# Controller-IOBoard.net
KiCad netlist of a schematic drawn in Altium Designer
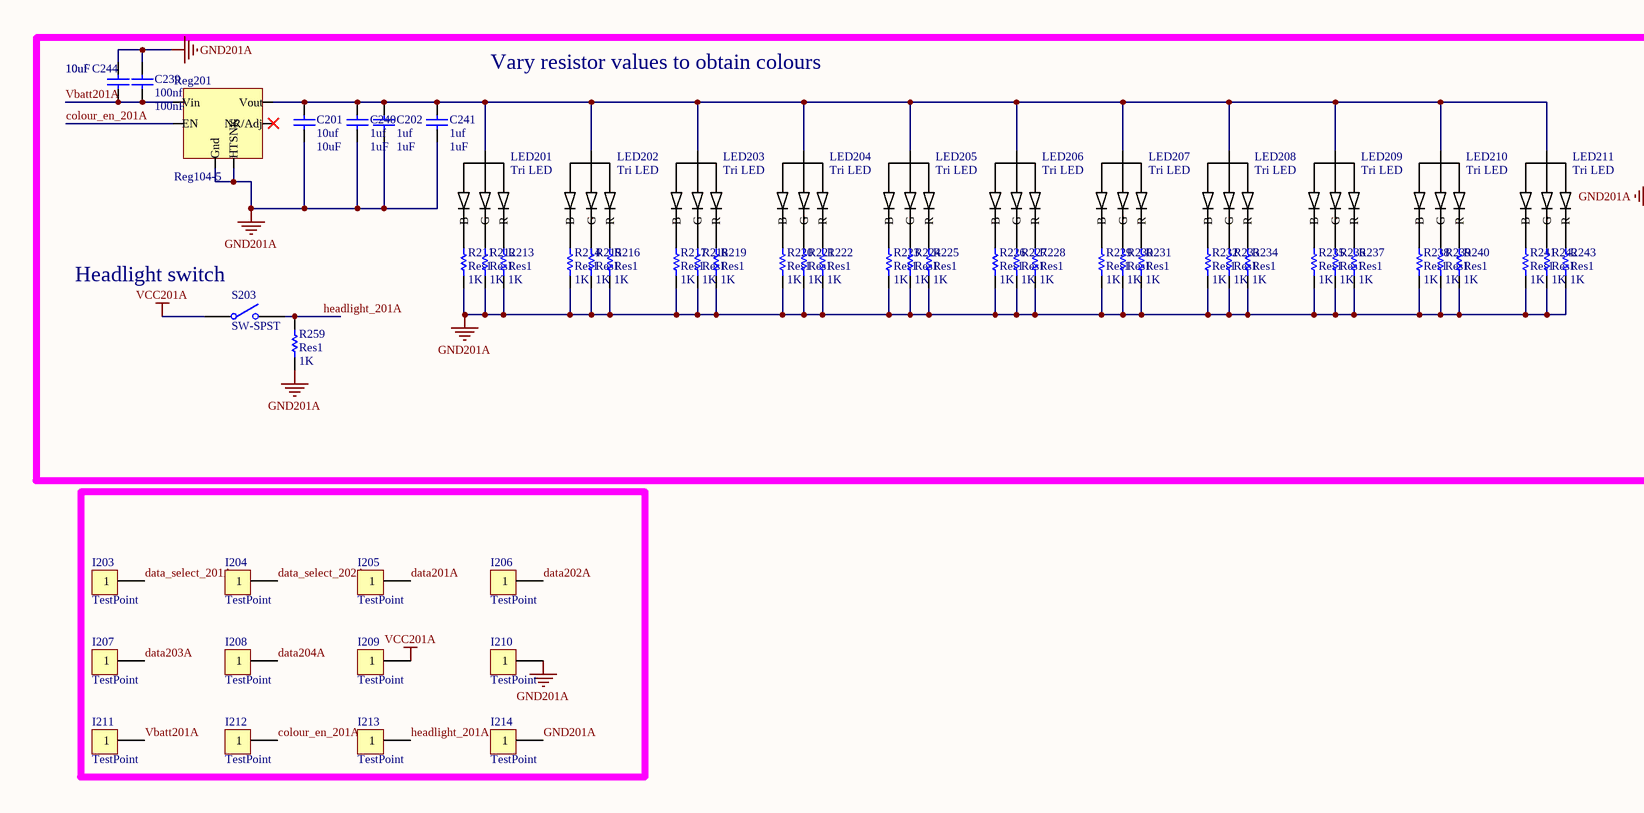
[diagram p0: Controller-IOBoard.SchDoc, left]
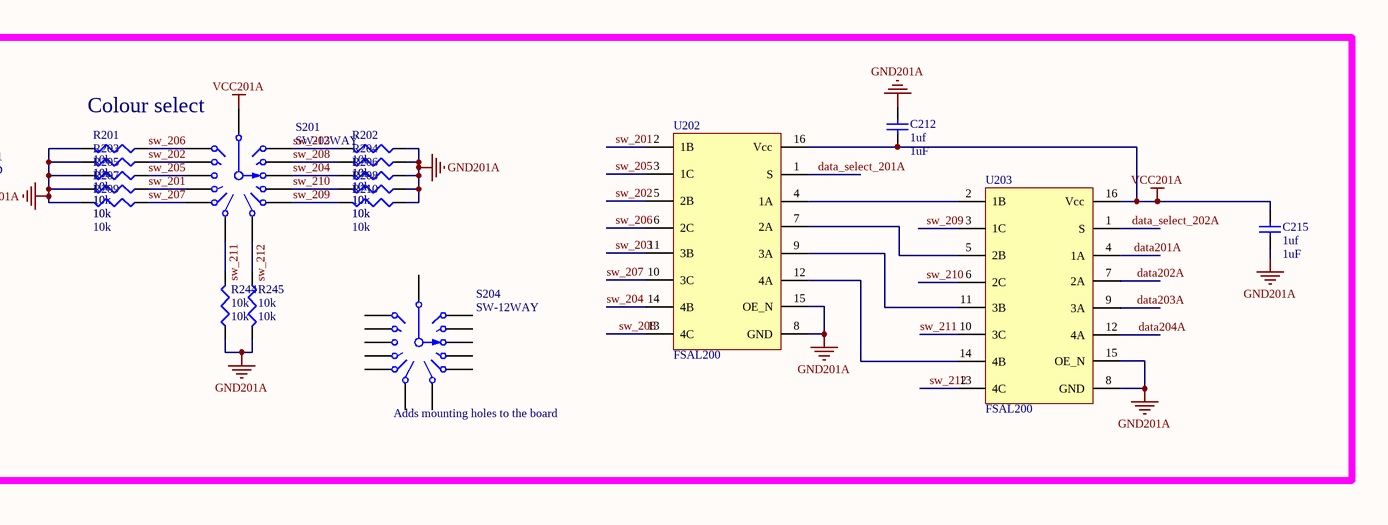
[diagram p1: Controller-IOBoard.SchDoc, right]

(export (version "E")
  (design (tool "Eeschema 10.0.6"))
  (components
    (comp (ref "C201")
      (value "10uf")
      (footprint "0805")
      (description "Capacitor (Semiconductor SIM Model)")
      (fields (field (name "ALTIUM_VALUE") "10uF") (field (name "PUBLISHER") "Altium Limited"))
      (libsource (lib "Miscellaneous Devices") (part "Cap Semi"))
    )
    (comp (ref "C202")
      (value "1uf")
      (footprint "0603")
      (description "Capacitor (Semiconductor SIM Model)")
      (fields (field (name "ALTIUM_VALUE") "1uF") (field (name "PUBLISHER") "Altium Limited"))
      (libsource (lib "Miscellaneous Devices") (part "Cap Semi"))
    )
    (comp (ref "C212")
      (value "1uf")
      (footprint "0603")
      (description "Capacitor (Semiconductor SIM Model)")
      (fields (field (name "ALTIUM_VALUE") "1uF") (field (name "PUBLISHER") "Altium Limited"))
      (libsource (lib "Miscellaneous Devices") (part "Cap Semi"))
    )
    (comp (ref "C215")
      (value "1uf")
      (footprint "0603")
      (description "Capacitor (Semiconductor SIM Model)")
      (fields (field (name "ALTIUM_VALUE") "1uF") (field (name "PUBLISHER") "Altium Limited"))
      (libsource (lib "Miscellaneous Devices") (part "Cap Semi"))
    )
    (comp (ref "C239")
      (value "100nf")
      (footprint "0603")
      (description "Capacitor (Semiconductor SIM Model)")
      (fields (field (name "ALTIUM_VALUE") "100nF") (field (name "PUBLISHER") "Altium Limited"))
      (libsource (lib "Miscellaneous Devices") (part "Cap Semi"))
    )
    (comp (ref "C240")
      (value "1uf")
      (footprint "0603")
      (description "Capacitor (Semiconductor SIM Model)")
      (fields (field (name "ALTIUM_VALUE") "1uF") (field (name "PUBLISHER") "Altium Limited"))
      (libsource (lib "Miscellaneous Devices") (part "Cap Semi"))
    )
    (comp (ref "C241")
      (value "1uf")
      (footprint "0603")
      (description "Capacitor (Semiconductor SIM Model)")
      (fields (field (name "ALTIUM_VALUE") "1uF") (field (name "PUBLISHER") "Altium Limited"))
      (libsource (lib "Miscellaneous Devices") (part "Cap Semi"))
    )
    (comp (ref "C244")
      (value "10uf")
      (footprint "0805")
      (description "Capacitor (Semiconductor SIM Model)")
      (fields (field (name "ALTIUM_VALUE") "10uF") (field (name "PUBLISHER") "Altium Limited"))
      (libsource (lib "Miscellaneous Devices") (part "Cap Semi"))
    )
    (comp (ref "I203")
      (value "TestPoint")
      (footprint "TestPoint")
      (libsource (lib "Schlib1") (part "TestPoint"))
    )
    (comp (ref "I204")
      (value "TestPoint")
      (footprint "TestPoint")
      (libsource (lib "Schlib1") (part "TestPoint"))
    )
    (comp (ref "I205")
      (value "TestPoint")
      (footprint "TestPoint")
      (libsource (lib "Schlib1") (part "TestPoint"))
    )
    (comp (ref "I206")
      (value "TestPoint")
      (footprint "TestPoint")
      (libsource (lib "Schlib1") (part "TestPoint"))
    )
    (comp (ref "I207")
      (value "TestPoint")
      (footprint "TestPoint")
      (libsource (lib "Schlib1") (part "TestPoint"))
    )
    (comp (ref "I208")
      (value "TestPoint")
      (footprint "TestPoint")
      (libsource (lib "Schlib1") (part "TestPoint"))
    )
    (comp (ref "I209")
      (value "TestPoint")
      (footprint "TestPoint")
      (libsource (lib "Schlib1") (part "TestPoint"))
    )
    (comp (ref "I210")
      (value "TestPoint")
      (footprint "TestPoint")
      (libsource (lib "Schlib1") (part "TestPoint"))
    )
    (comp (ref "I211")
      (value "TestPoint")
      (footprint "TestPoint")
      (libsource (lib "Schlib1") (part "TestPoint"))
    )
    (comp (ref "I212")
      (value "TestPoint")
      (footprint "TestPoint")
      (libsource (lib "Schlib1") (part "TestPoint"))
    )
    (comp (ref "I213")
      (value "TestPoint")
      (footprint "TestPoint")
      (libsource (lib "Schlib1") (part "TestPoint"))
    )
    (comp (ref "I214")
      (value "TestPoint")
      (footprint "TestPoint")
      (libsource (lib "Schlib1") (part "TestPoint"))
    )
    (comp (ref "LED201")
      (value "Tri LED")
      (footprint "CLV1A-FKB")
      (libsource (lib "Schlib1") (part "Tri LED"))
    )
    (comp (ref "LED202")
      (value "Tri LED")
      (footprint "CLV1A-FKB")
      (libsource (lib "Schlib1") (part "Tri LED"))
    )
    (comp (ref "LED203")
      (value "Tri LED")
      (footprint "CLV1A-FKB")
      (libsource (lib "Schlib1") (part "Tri LED"))
    )
    (comp (ref "LED204")
      (value "Tri LED")
      (footprint "CLV1A-FKB")
      (libsource (lib "Schlib1") (part "Tri LED"))
    )
    (comp (ref "LED205")
      (value "Tri LED")
      (footprint "CLV1A-FKB")
      (libsource (lib "Schlib1") (part "Tri LED"))
    )
    (comp (ref "LED206")
      (value "Tri LED")
      (footprint "CLV1A-FKB")
      (libsource (lib "Schlib1") (part "Tri LED"))
    )
    (comp (ref "LED207")
      (value "Tri LED")
      (footprint "CLV1A-FKB")
      (libsource (lib "Schlib1") (part "Tri LED"))
    )
    (comp (ref "LED208")
      (value "Tri LED")
      (footprint "CLV1A-FKB")
      (libsource (lib "Schlib1") (part "Tri LED"))
    )
    (comp (ref "LED209")
      (value "Tri LED")
      (footprint "CLV1A-FKB")
      (libsource (lib "Schlib1") (part "Tri LED"))
    )
    (comp (ref "LED210")
      (value "Tri LED")
      (footprint "CLV1A-FKB")
      (libsource (lib "Schlib1") (part "Tri LED"))
    )
    (comp (ref "LED211")
      (value "Tri LED")
      (footprint "CLV1A-FKB")
      (libsource (lib "Schlib1") (part "Tri LED"))
    )
    (comp (ref "R201")
      (value "10k")
      (footprint "0603")
      (description "Resistor")
      (fields (field (name "ALTIUM_VALUE") "10k") (field (name "PUBLISHER") "Altium Limited"))
      (libsource (lib "Miscellaneous Devices") (part "Res3"))
    )
    (comp (ref "R202")
      (value "10k")
      (footprint "0603")
      (description "Resistor")
      (fields (field (name "ALTIUM_VALUE") "10k") (field (name "PUBLISHER") "Altium Limited"))
      (libsource (lib "Miscellaneous Devices") (part "Res3"))
    )
    (comp (ref "R203")
      (value "10k")
      (footprint "0603")
      (description "Resistor")
      (fields (field (name "ALTIUM_VALUE") "10k") (field (name "PUBLISHER") "Altium Limited"))
      (libsource (lib "Miscellaneous Devices") (part "Res3"))
    )
    (comp (ref "R204")
      (value "10k")
      (footprint "0603")
      (description "Resistor")
      (fields (field (name "ALTIUM_VALUE") "10k") (field (name "PUBLISHER") "Altium Limited"))
      (libsource (lib "Miscellaneous Devices") (part "Res3"))
    )
    (comp (ref "R205")
      (value "10k")
      (footprint "0603")
      (description "Resistor")
      (fields (field (name "ALTIUM_VALUE") "10k") (field (name "PUBLISHER") "Altium Limited"))
      (libsource (lib "Miscellaneous Devices") (part "Res3"))
    )
    (comp (ref "R206")
      (value "10k")
      (footprint "0603")
      (description "Resistor")
      (fields (field (name "ALTIUM_VALUE") "10k") (field (name "PUBLISHER") "Altium Limited"))
      (libsource (lib "Miscellaneous Devices") (part "Res3"))
    )
    (comp (ref "R207")
      (value "10k")
      (footprint "0603")
      (description "Resistor")
      (fields (field (name "ALTIUM_VALUE") "10k") (field (name "PUBLISHER") "Altium Limited"))
      (libsource (lib "Miscellaneous Devices") (part "Res3"))
    )
    (comp (ref "R208")
      (value "10k")
      (footprint "0603")
      (description "Resistor")
      (fields (field (name "ALTIUM_VALUE") "10k") (field (name "PUBLISHER") "Altium Limited"))
      (libsource (lib "Miscellaneous Devices") (part "Res3"))
    )
    (comp (ref "R209")
      (value "10k")
      (footprint "0603")
      (description "Resistor")
      (fields (field (name "ALTIUM_VALUE") "10k") (field (name "PUBLISHER") "Altium Limited"))
      (libsource (lib "Miscellaneous Devices") (part "Res3"))
    )
    (comp (ref "R210")
      (value "10k")
      (footprint "0603")
      (description "Resistor")
      (fields (field (name "ALTIUM_VALUE") "10k") (field (name "PUBLISHER") "Altium Limited"))
      (libsource (lib "Miscellaneous Devices") (part "Res3"))
    )
    (comp (ref "R211")
      (value "Res1")
      (footprint "0805")
      (description "Resistor")
      (fields (field (name "ALTIUM_VALUE") "1K") (field (name "PUBLISHER") "Altium Limited"))
      (libsource (lib "Miscellaneous Devices") (part "Res1"))
    )
    (comp (ref "R212")
      (value "Res1")
      (footprint "0805")
      (description "Resistor")
      (fields (field (name "ALTIUM_VALUE") "1K") (field (name "PUBLISHER") "Altium Limited"))
      (libsource (lib "Miscellaneous Devices") (part "Res1"))
    )
    (comp (ref "R213")
      (value "Res1")
      (footprint "0805")
      (description "Resistor")
      (fields (field (name "ALTIUM_VALUE") "1K") (field (name "PUBLISHER") "Altium Limited"))
      (libsource (lib "Miscellaneous Devices") (part "Res1"))
    )
    (comp (ref "R214")
      (value "Res1")
      (footprint "0805")
      (description "Resistor")
      (fields (field (name "ALTIUM_VALUE") "1K") (field (name "PUBLISHER") "Altium Limited"))
      (libsource (lib "Miscellaneous Devices") (part "Res1"))
    )
    (comp (ref "R215")
      (value "Res1")
      (footprint "0805")
      (description "Resistor")
      (fields (field (name "ALTIUM_VALUE") "1K") (field (name "PUBLISHER") "Altium Limited"))
      (libsource (lib "Miscellaneous Devices") (part "Res1"))
    )
    (comp (ref "R216")
      (value "Res1")
      (footprint "0805")
      (description "Resistor")
      (fields (field (name "ALTIUM_VALUE") "1K") (field (name "PUBLISHER") "Altium Limited"))
      (libsource (lib "Miscellaneous Devices") (part "Res1"))
    )
    (comp (ref "R217")
      (value "Res1")
      (footprint "0805")
      (description "Resistor")
      (fields (field (name "ALTIUM_VALUE") "1K") (field (name "PUBLISHER") "Altium Limited"))
      (libsource (lib "Miscellaneous Devices") (part "Res1"))
    )
    (comp (ref "R218")
      (value "Res1")
      (footprint "0805")
      (description "Resistor")
      (fields (field (name "ALTIUM_VALUE") "1K") (field (name "PUBLISHER") "Altium Limited"))
      (libsource (lib "Miscellaneous Devices") (part "Res1"))
    )
    (comp (ref "R219")
      (value "Res1")
      (footprint "0805")
      (description "Resistor")
      (fields (field (name "ALTIUM_VALUE") "1K") (field (name "PUBLISHER") "Altium Limited"))
      (libsource (lib "Miscellaneous Devices") (part "Res1"))
    )
    (comp (ref "R220")
      (value "Res1")
      (footprint "0805")
      (description "Resistor")
      (fields (field (name "ALTIUM_VALUE") "1K") (field (name "PUBLISHER") "Altium Limited"))
      (libsource (lib "Miscellaneous Devices") (part "Res1"))
    )
    (comp (ref "R221")
      (value "Res1")
      (footprint "0805")
      (description "Resistor")
      (fields (field (name "ALTIUM_VALUE") "1K") (field (name "PUBLISHER") "Altium Limited"))
      (libsource (lib "Miscellaneous Devices") (part "Res1"))
    )
    (comp (ref "R222")
      (value "Res1")
      (footprint "0805")
      (description "Resistor")
      (fields (field (name "ALTIUM_VALUE") "1K") (field (name "PUBLISHER") "Altium Limited"))
      (libsource (lib "Miscellaneous Devices") (part "Res1"))
    )
    (comp (ref "R223")
      (value "Res1")
      (footprint "0805")
      (description "Resistor")
      (fields (field (name "ALTIUM_VALUE") "1K") (field (name "PUBLISHER") "Altium Limited"))
      (libsource (lib "Miscellaneous Devices") (part "Res1"))
    )
    (comp (ref "R224")
      (value "Res1")
      (footprint "0805")
      (description "Resistor")
      (fields (field (name "ALTIUM_VALUE") "1K") (field (name "PUBLISHER") "Altium Limited"))
      (libsource (lib "Miscellaneous Devices") (part "Res1"))
    )
    (comp (ref "R225")
      (value "Res1")
      (footprint "0805")
      (description "Resistor")
      (fields (field (name "ALTIUM_VALUE") "1K") (field (name "PUBLISHER") "Altium Limited"))
      (libsource (lib "Miscellaneous Devices") (part "Res1"))
    )
    (comp (ref "R226")
      (value "Res1")
      (footprint "0805")
      (description "Resistor")
      (fields (field (name "ALTIUM_VALUE") "1K") (field (name "PUBLISHER") "Altium Limited"))
      (libsource (lib "Miscellaneous Devices") (part "Res1"))
    )
    (comp (ref "R227")
      (value "Res1")
      (footprint "0805")
      (description "Resistor")
      (fields (field (name "ALTIUM_VALUE") "1K") (field (name "PUBLISHER") "Altium Limited"))
      (libsource (lib "Miscellaneous Devices") (part "Res1"))
    )
    (comp (ref "R228")
      (value "Res1")
      (footprint "0805")
      (description "Resistor")
      (fields (field (name "ALTIUM_VALUE") "1K") (field (name "PUBLISHER") "Altium Limited"))
      (libsource (lib "Miscellaneous Devices") (part "Res1"))
    )
    (comp (ref "R229")
      (value "Res1")
      (footprint "0805")
      (description "Resistor")
      (fields (field (name "ALTIUM_VALUE") "1K") (field (name "PUBLISHER") "Altium Limited"))
      (libsource (lib "Miscellaneous Devices") (part "Res1"))
    )
    (comp (ref "R230")
      (value "Res1")
      (footprint "0805")
      (description "Resistor")
      (fields (field (name "ALTIUM_VALUE") "1K") (field (name "PUBLISHER") "Altium Limited"))
      (libsource (lib "Miscellaneous Devices") (part "Res1"))
    )
    (comp (ref "R231")
      (value "Res1")
      (footprint "0805")
      (description "Resistor")
      (fields (field (name "ALTIUM_VALUE") "1K") (field (name "PUBLISHER") "Altium Limited"))
      (libsource (lib "Miscellaneous Devices") (part "Res1"))
    )
    (comp (ref "R232")
      (value "Res1")
      (footprint "0805")
      (description "Resistor")
      (fields (field (name "ALTIUM_VALUE") "1K") (field (name "PUBLISHER") "Altium Limited"))
      (libsource (lib "Miscellaneous Devices") (part "Res1"))
    )
    (comp (ref "R233")
      (value "Res1")
      (footprint "0805")
      (description "Resistor")
      (fields (field (name "ALTIUM_VALUE") "1K") (field (name "PUBLISHER") "Altium Limited"))
      (libsource (lib "Miscellaneous Devices") (part "Res1"))
    )
    (comp (ref "R234")
      (value "Res1")
      (footprint "0805")
      (description "Resistor")
      (fields (field (name "ALTIUM_VALUE") "1K") (field (name "PUBLISHER") "Altium Limited"))
      (libsource (lib "Miscellaneous Devices") (part "Res1"))
    )
    (comp (ref "R235")
      (value "Res1")
      (footprint "0805")
      (description "Resistor")
      (fields (field (name "ALTIUM_VALUE") "1K") (field (name "PUBLISHER") "Altium Limited"))
      (libsource (lib "Miscellaneous Devices") (part "Res1"))
    )
    (comp (ref "R236")
      (value "Res1")
      (footprint "0805")
      (description "Resistor")
      (fields (field (name "ALTIUM_VALUE") "1K") (field (name "PUBLISHER") "Altium Limited"))
      (libsource (lib "Miscellaneous Devices") (part "Res1"))
    )
    (comp (ref "R237")
      (value "Res1")
      (footprint "0805")
      (description "Resistor")
      (fields (field (name "ALTIUM_VALUE") "1K") (field (name "PUBLISHER") "Altium Limited"))
      (libsource (lib "Miscellaneous Devices") (part "Res1"))
    )
    (comp (ref "R238")
      (value "Res1")
      (footprint "0805")
      (description "Resistor")
      (fields (field (name "ALTIUM_VALUE") "1K") (field (name "PUBLISHER") "Altium Limited"))
      (libsource (lib "Miscellaneous Devices") (part "Res1"))
    )
    (comp (ref "R239")
      (value "Res1")
      (footprint "0805")
      (description "Resistor")
      (fields (field (name "ALTIUM_VALUE") "1K") (field (name "PUBLISHER") "Altium Limited"))
      (libsource (lib "Miscellaneous Devices") (part "Res1"))
    )
    (comp (ref "R240")
      (value "Res1")
      (footprint "0805")
      (description "Resistor")
      (fields (field (name "ALTIUM_VALUE") "1K") (field (name "PUBLISHER") "Altium Limited"))
      (libsource (lib "Miscellaneous Devices") (part "Res1"))
    )
    (comp (ref "R241")
      (value "Res1")
      (footprint "0805")
      (description "Resistor")
      (fields (field (name "ALTIUM_VALUE") "1K") (field (name "PUBLISHER") "Altium Limited"))
      (libsource (lib "Miscellaneous Devices") (part "Res1"))
    )
    (comp (ref "R242")
      (value "Res1")
      (footprint "0805")
      (description "Resistor")
      (fields (field (name "ALTIUM_VALUE") "1K") (field (name "PUBLISHER") "Altium Limited"))
      (libsource (lib "Miscellaneous Devices") (part "Res1"))
    )
    (comp (ref "R243")
      (value "Res1")
      (footprint "0805")
      (description "Resistor")
      (fields (field (name "ALTIUM_VALUE") "1K") (field (name "PUBLISHER") "Altium Limited"))
      (libsource (lib "Miscellaneous Devices") (part "Res1"))
    )
    (comp (ref "R244")
      (value "10k")
      (footprint "0603")
      (description "Resistor")
      (fields (field (name "ALTIUM_VALUE") "10k") (field (name "PUBLISHER") "Altium Limited"))
      (libsource (lib "Miscellaneous Devices") (part "Res3"))
    )
    (comp (ref "R245")
      (value "10k")
      (footprint "0603")
      (description "Resistor")
      (fields (field (name "ALTIUM_VALUE") "10k") (field (name "PUBLISHER") "Altium Limited"))
      (libsource (lib "Miscellaneous Devices") (part "Res3"))
    )
    (comp (ref "R259")
      (value "Res1")
      (footprint "0805")
      (description "Resistor")
      (fields (field (name "ALTIUM_VALUE") "1K") (field (name "PUBLISHER") "Altium Limited"))
      (libsource (lib "Miscellaneous Devices") (part "Res1"))
    )
    (comp (ref "Reg201")
      (value "Reg104-5")
      (footprint "REG104-5-DDPAK5")
      (libsource (lib "Schlib1") (part "Reg104-5"))
    )
    (comp (ref "S201")
      (value "SW-12WAY")
      (footprint "switch pad layout")
      (description "12 Way Switch")
      (fields (field (name "PUBLISHER") "Altium Limited"))
      (libsource (lib "Miscellaneous Devices") (part "SW-12WAY"))
    )
    (comp (ref "S203")
      (value "SW-SPST")
      (footprint "2 pin switch (surface mount)")
      (description "Single-Pole, Single-Throw Switch")
      (fields (field (name "PUBLISHER") "Altium Limited"))
      (libsource (lib "Miscellaneous Devices") (part "SW-SPST"))
    )
    (comp (ref "S204")
      (value "SW-12WAY")
      (footprint "12 pole switch")
      (description "12 Way Switch")
      (fields (field (name "PUBLISHER") "Altium Limited"))
      (libsource (lib "Miscellaneous Devices") (part "SW-12WAY"))
    )
    (comp (ref "U202")
      (value "FSAL200")
      (footprint "FSAL200-16QSOP")
      (description "ST Quad Bi-Directional Logic Switch")
      (libsource (lib "Schlib1") (part "FSAL200"))
    )
    (comp (ref "U203")
      (value "FSAL200")
      (footprint "FSAL200-16QSOP")
      (description "ST Quad Bi-Directional Logic Switch")
      (libsource (lib "Schlib1") (part "FSAL200"))
    )
  )
  (nets
    (net (code "1") (name "/Vbatt201A") (class "Default")
      (node (ref "C239") (pin "1") (pinfunction "1_1") (pintype "passive"))
      (node (ref "C244") (pin "1") (pinfunction "1_1") (pintype "passive"))
      (node (ref "I211") (pin "1") (pinfunction "1_1") (pintype "passive"))
      (node (ref "Reg201") (pin "1") (pinfunction "Vin_1") (pintype "passive"))
    )
    (net (code "2") (name "/colour_en_201A") (class "Default")
      (node (ref "I212") (pin "1") (pinfunction "1_1") (pintype "passive"))
      (node (ref "Reg201") (pin "5") (pinfunction "EN_5") (pintype "passive"))
    )
    (net (code "3") (name "/data201A") (class "Default")
      (node (ref "I205") (pin "1") (pinfunction "1_1") (pintype "passive"))
      (node (ref "U203") (pin "4") (pinfunction "1A_4") (pintype "passive"))
    )
    (net (code "4") (name "/data202A") (class "Default")
      (node (ref "I206") (pin "1") (pinfunction "1_1") (pintype "passive"))
      (node (ref "U203") (pin "7") (pinfunction "2A_7") (pintype "passive"))
    )
    (net (code "5") (name "/data203A") (class "Default")
      (node (ref "I207") (pin "1") (pinfunction "1_1") (pintype "passive"))
      (node (ref "U203") (pin "9") (pinfunction "3A_9") (pintype "passive"))
    )
    (net (code "6") (name "/data204A") (class "Default")
      (node (ref "I208") (pin "1") (pinfunction "1_1") (pintype "passive"))
      (node (ref "U203") (pin "12") (pinfunction "4A_12") (pintype "passive"))
    )
    (net (code "7") (name "/data_select_201A") (class "Default")
      (node (ref "I203") (pin "1") (pinfunction "1_1") (pintype "passive"))
      (node (ref "U202") (pin "1") (pinfunction "S_1") (pintype "passive"))
    )
    (net (code "8") (name "/data_select_202A") (class "Default")
      (node (ref "I204") (pin "1") (pinfunction "1_1") (pintype "passive"))
      (node (ref "U203") (pin "1") (pinfunction "S_1") (pintype "passive"))
    )
    (net (code "9") (name "/headlight_201A") (class "Default")
      (node (ref "I213") (pin "1") (pinfunction "1_1") (pintype "passive"))
      (node (ref "R259") (pin "1") (pinfunction "1_1") (pintype "passive"))
      (node (ref "S203") (pin "2") (pinfunction "NO_2") (pintype "passive"))
    )
    (net (code "10") (name "/sw_201") (class "Default")
      (node (ref "R207") (pin "1") (pinfunction "1_1") (pintype "passive"))
      (node (ref "S201") (pin "5") (pinfunction "5_5") (pintype "passive"))
      (node (ref "U202") (pin "2") (pinfunction "1B_2") (pintype "passive"))
    )
    (net (code "11") (name "/sw_202") (class "Default")
      (node (ref "R203") (pin "1") (pinfunction "1_1") (pintype "passive"))
      (node (ref "S201") (pin "2") (pinfunction "2_2") (pintype "passive"))
      (node (ref "U202") (pin "5") (pinfunction "2B_5") (pintype "passive"))
    )
    (net (code "12") (name "/sw_203") (class "Default")
      (node (ref "R202") (pin "2") (pinfunction "2_2") (pintype "passive"))
      (node (ref "S201") (pin "7") (pinfunction "7_7") (pintype "passive"))
      (node (ref "U202") (pin "11") (pinfunction "3B_11") (pintype "passive"))
    )
    (net (code "13") (name "/sw_204") (class "Default")
      (node (ref "R206") (pin "2") (pinfunction "2_2") (pintype "passive"))
      (node (ref "S201") (pin "9") (pinfunction "9_9") (pintype "passive"))
      (node (ref "U202") (pin "14") (pinfunction "4B_14") (pintype "passive"))
    )
    (net (code "14") (name "/sw_205") (class "Default")
      (node (ref "R205") (pin "1") (pinfunction "1_1") (pintype "passive"))
      (node (ref "S201") (pin "3") (pinfunction "3_3") (pintype "passive"))
      (node (ref "U202") (pin "3") (pinfunction "1C_3") (pintype "passive"))
    )
    (net (code "15") (name "/sw_206") (class "Default")
      (node (ref "R201") (pin "1") (pinfunction "1_1") (pintype "passive"))
      (node (ref "S201") (pin "1") (pinfunction "1_1") (pintype "passive"))
      (node (ref "U202") (pin "6") (pinfunction "2C_6") (pintype "passive"))
    )
    (net (code "16") (name "/sw_207") (class "Default")
      (node (ref "R209") (pin "1") (pinfunction "1_1") (pintype "passive"))
      (node (ref "S201") (pin "6") (pinfunction "6_6") (pintype "passive"))
      (node (ref "U202") (pin "10") (pinfunction "3C_10") (pintype "passive"))
    )
    (net (code "17") (name "/sw_208") (class "Default")
      (node (ref "R204") (pin "2") (pinfunction "2_2") (pintype "passive"))
      (node (ref "S201") (pin "8") (pinfunction "8_8") (pintype "passive"))
      (node (ref "U202") (pin "13") (pinfunction "4C_13") (pintype "passive"))
    )
    (net (code "18") (name "/sw_209") (class "Default")
      (node (ref "R210") (pin "2") (pinfunction "2_2") (pintype "passive"))
      (node (ref "S201") (pin "11") (pinfunction "11_11") (pintype "passive"))
      (node (ref "U203") (pin "3") (pinfunction "1C_3") (pintype "passive"))
    )
    (net (code "19") (name "/sw_210") (class "Default")
      (node (ref "R208") (pin "2") (pinfunction "2_2") (pintype "passive"))
      (node (ref "S201") (pin "10") (pinfunction "10_10") (pintype "passive"))
      (node (ref "U203") (pin "6") (pinfunction "2C_6") (pintype "passive"))
    )
    (net (code "20") (name "/sw_211") (class "Default")
      (node (ref "R244") (pin "2") (pinfunction "2_2") (pintype "passive"))
      (node (ref "S201") (pin "12") (pinfunction "12_12") (pintype "passive"))
      (node (ref "U203") (pin "10") (pinfunction "3C_10") (pintype "passive"))
    )
    (net (code "21") (name "/sw_212") (class "Default")
      (node (ref "R245") (pin "1") (pinfunction "1_1") (pintype "passive"))
      (node (ref "S201") (pin "13") (pinfunction "13_13") (pintype "passive"))
      (node (ref "U203") (pin "13") (pinfunction "4C_13") (pintype "passive"))
    )
    (net (code "22") (name "GND201A") (class "Default")
      (node (ref "C201") (pin "1") (pinfunction "1_1") (pintype "passive"))
      (node (ref "C202") (pin "1") (pinfunction "1_1") (pintype "passive"))
      (node (ref "C212") (pin "2") (pinfunction "2_2") (pintype "passive"))
      (node (ref "C215") (pin "1") (pinfunction "1_1") (pintype "passive"))
      (node (ref "C239") (pin "2") (pinfunction "2_2") (pintype "passive"))
      (node (ref "C240") (pin "1") (pinfunction "1_1") (pintype "passive"))
      (node (ref "C241") (pin "1") (pinfunction "1_1") (pintype "passive"))
      (node (ref "C244") (pin "2") (pinfunction "2_2") (pintype "passive"))
      (node (ref "I210") (pin "1") (pinfunction "1_1") (pintype "passive"))
      (node (ref "I214") (pin "1") (pinfunction "1_1") (pintype "passive"))
      (node (ref "R201") (pin "2") (pinfunction "2_2") (pintype "passive"))
      (node (ref "R202") (pin "1") (pinfunction "1_1") (pintype "passive"))
      (node (ref "R203") (pin "2") (pinfunction "2_2") (pintype "passive"))
      (node (ref "R204") (pin "1") (pinfunction "1_1") (pintype "passive"))
      (node (ref "R205") (pin "2") (pinfunction "2_2") (pintype "passive"))
      (node (ref "R206") (pin "1") (pinfunction "1_1") (pintype "passive"))
      (node (ref "R207") (pin "2") (pinfunction "2_2") (pintype "passive"))
      (node (ref "R208") (pin "1") (pinfunction "1_1") (pintype "passive"))
      (node (ref "R209") (pin "2") (pinfunction "2_2") (pintype "passive"))
      (node (ref "R210") (pin "1") (pinfunction "1_1") (pintype "passive"))
      (node (ref "R211") (pin "1") (pinfunction "1_1") (pintype "passive"))
      (node (ref "R212") (pin "1") (pinfunction "1_1") (pintype "passive"))
      (node (ref "R213") (pin "1") (pinfunction "1_1") (pintype "passive"))
      (node (ref "R214") (pin "1") (pinfunction "1_1") (pintype "passive"))
      (node (ref "R215") (pin "1") (pinfunction "1_1") (pintype "passive"))
      (node (ref "R216") (pin "1") (pinfunction "1_1") (pintype "passive"))
      (node (ref "R217") (pin "1") (pinfunction "1_1") (pintype "passive"))
      (node (ref "R218") (pin "1") (pinfunction "1_1") (pintype "passive"))
      (node (ref "R219") (pin "1") (pinfunction "1_1") (pintype "passive"))
      (node (ref "R220") (pin "1") (pinfunction "1_1") (pintype "passive"))
      (node (ref "R221") (pin "1") (pinfunction "1_1") (pintype "passive"))
      (node (ref "R222") (pin "1") (pinfunction "1_1") (pintype "passive"))
      (node (ref "R223") (pin "1") (pinfunction "1_1") (pintype "passive"))
      (node (ref "R224") (pin "1") (pinfunction "1_1") (pintype "passive"))
      (node (ref "R225") (pin "1") (pinfunction "1_1") (pintype "passive"))
      (node (ref "R226") (pin "1") (pinfunction "1_1") (pintype "passive"))
      (node (ref "R227") (pin "1") (pinfunction "1_1") (pintype "passive"))
      (node (ref "R228") (pin "1") (pinfunction "1_1") (pintype "passive"))
      (node (ref "R229") (pin "1") (pinfunction "1_1") (pintype "passive"))
      (node (ref "R230") (pin "1") (pinfunction "1_1") (pintype "passive"))
      (node (ref "R231") (pin "1") (pinfunction "1_1") (pintype "passive"))
      (node (ref "R232") (pin "1") (pinfunction "1_1") (pintype "passive"))
      (node (ref "R233") (pin "1") (pinfunction "1_1") (pintype "passive"))
      (node (ref "R234") (pin "1") (pinfunction "1_1") (pintype "passive"))
      (node (ref "R235") (pin "1") (pinfunction "1_1") (pintype "passive"))
      (node (ref "R236") (pin "1") (pinfunction "1_1") (pintype "passive"))
      (node (ref "R237") (pin "1") (pinfunction "1_1") (pintype "passive"))
      (node (ref "R238") (pin "1") (pinfunction "1_1") (pintype "passive"))
      (node (ref "R239") (pin "1") (pinfunction "1_1") (pintype "passive"))
      (node (ref "R240") (pin "1") (pinfunction "1_1") (pintype "passive"))
      (node (ref "R241") (pin "1") (pinfunction "1_1") (pintype "passive"))
      (node (ref "R242") (pin "1") (pinfunction "1_1") (pintype "passive"))
      (node (ref "R243") (pin "1") (pinfunction "1_1") (pintype "passive"))
      (node (ref "R244") (pin "1") (pinfunction "1_1") (pintype "passive"))
      (node (ref "R245") (pin "2") (pinfunction "2_2") (pintype "passive"))
      (node (ref "R259") (pin "2") (pinfunction "2_2") (pintype "passive"))
      (node (ref "Reg201") (pin "3") (pinfunction "Gnd_3") (pintype "passive"))
      (node (ref "Reg201") (pin "6") (pinfunction "HTSNK_6") (pintype "passive"))
      (node (ref "U202") (pin "15") (pinfunction "OE_N_15") (pintype "passive"))
      (node (ref "U202") (pin "8") (pinfunction "GND_8") (pintype "passive"))
      (node (ref "U203") (pin "15") (pinfunction "OE_N_15") (pintype "passive"))
      (node (ref "U203") (pin "8") (pinfunction "GND_8") (pintype "passive"))
    )
    (net (code "23") (name "Net-(LED201-B)") (class "Default")
      (node (ref "LED201") (pin "3") (pinfunction "B_3") (pintype "passive"))
      (node (ref "R211") (pin "2") (pinfunction "2_2") (pintype "passive"))
    )
    (net (code "24") (name "Net-(LED201-Common)") (class "Default")
      (node (ref "C201") (pin "2") (pinfunction "2_2") (pintype "passive"))
      (node (ref "C202") (pin "2") (pinfunction "2_2") (pintype "passive"))
      (node (ref "C240") (pin "2") (pinfunction "2_2") (pintype "passive"))
      (node (ref "C241") (pin "2") (pinfunction "2_2") (pintype "passive"))
      (node (ref "LED201") (pin "2") (pinfunction "Common_2") (pintype "passive"))
      (node (ref "LED202") (pin "2") (pinfunction "Common_2") (pintype "passive"))
      (node (ref "LED203") (pin "2") (pinfunction "Common_2") (pintype "passive"))
      (node (ref "LED204") (pin "2") (pinfunction "Common_2") (pintype "passive"))
      (node (ref "LED205") (pin "2") (pinfunction "Common_2") (pintype "passive"))
      (node (ref "LED206") (pin "2") (pinfunction "Common_2") (pintype "passive"))
      (node (ref "LED207") (pin "2") (pinfunction "Common_2") (pintype "passive"))
      (node (ref "LED208") (pin "2") (pinfunction "Common_2") (pintype "passive"))
      (node (ref "LED209") (pin "2") (pinfunction "Common_2") (pintype "passive"))
      (node (ref "LED210") (pin "2") (pinfunction "Common_2") (pintype "passive"))
      (node (ref "LED211") (pin "2") (pinfunction "Common_2") (pintype "passive"))
      (node (ref "Reg201") (pin "2") (pinfunction "Vout_2") (pintype "passive"))
    )
    (net (code "25") (name "Net-(LED201-G)") (class "Default")
      (node (ref "LED201") (pin "4") (pinfunction "G_4") (pintype "passive"))
      (node (ref "R212") (pin "2") (pinfunction "2_2") (pintype "passive"))
    )
    (net (code "26") (name "Net-(LED201-R)") (class "Default")
      (node (ref "LED201") (pin "1") (pinfunction "R_1") (pintype "passive"))
      (node (ref "R213") (pin "2") (pinfunction "2_2") (pintype "passive"))
    )
    (net (code "27") (name "Net-(LED202-B)") (class "Default")
      (node (ref "LED202") (pin "3") (pinfunction "B_3") (pintype "passive"))
      (node (ref "R214") (pin "2") (pinfunction "2_2") (pintype "passive"))
    )
    (net (code "28") (name "Net-(LED202-G)") (class "Default")
      (node (ref "LED202") (pin "4") (pinfunction "G_4") (pintype "passive"))
      (node (ref "R215") (pin "2") (pinfunction "2_2") (pintype "passive"))
    )
    (net (code "29") (name "Net-(LED202-R)") (class "Default")
      (node (ref "LED202") (pin "1") (pinfunction "R_1") (pintype "passive"))
      (node (ref "R216") (pin "2") (pinfunction "2_2") (pintype "passive"))
    )
    (net (code "30") (name "Net-(LED203-B)") (class "Default")
      (node (ref "LED203") (pin "3") (pinfunction "B_3") (pintype "passive"))
      (node (ref "R217") (pin "2") (pinfunction "2_2") (pintype "passive"))
    )
    (net (code "31") (name "Net-(LED203-G)") (class "Default")
      (node (ref "LED203") (pin "4") (pinfunction "G_4") (pintype "passive"))
      (node (ref "R218") (pin "2") (pinfunction "2_2") (pintype "passive"))
    )
    (net (code "32") (name "Net-(LED203-R)") (class "Default")
      (node (ref "LED203") (pin "1") (pinfunction "R_1") (pintype "passive"))
      (node (ref "R219") (pin "2") (pinfunction "2_2") (pintype "passive"))
    )
    (net (code "33") (name "Net-(LED204-B)") (class "Default")
      (node (ref "LED204") (pin "3") (pinfunction "B_3") (pintype "passive"))
      (node (ref "R220") (pin "2") (pinfunction "2_2") (pintype "passive"))
    )
    (net (code "34") (name "Net-(LED204-G)") (class "Default")
      (node (ref "LED204") (pin "4") (pinfunction "G_4") (pintype "passive"))
      (node (ref "R221") (pin "2") (pinfunction "2_2") (pintype "passive"))
    )
    (net (code "35") (name "Net-(LED204-R)") (class "Default")
      (node (ref "LED204") (pin "1") (pinfunction "R_1") (pintype "passive"))
      (node (ref "R222") (pin "2") (pinfunction "2_2") (pintype "passive"))
    )
    (net (code "36") (name "Net-(LED205-B)") (class "Default")
      (node (ref "LED205") (pin "3") (pinfunction "B_3") (pintype "passive"))
      (node (ref "R223") (pin "2") (pinfunction "2_2") (pintype "passive"))
    )
    (net (code "37") (name "Net-(LED205-G)") (class "Default")
      (node (ref "LED205") (pin "4") (pinfunction "G_4") (pintype "passive"))
      (node (ref "R224") (pin "2") (pinfunction "2_2") (pintype "passive"))
    )
    (net (code "38") (name "Net-(LED205-R)") (class "Default")
      (node (ref "LED205") (pin "1") (pinfunction "R_1") (pintype "passive"))
      (node (ref "R225") (pin "2") (pinfunction "2_2") (pintype "passive"))
    )
    (net (code "39") (name "Net-(LED206-B)") (class "Default")
      (node (ref "LED206") (pin "3") (pinfunction "B_3") (pintype "passive"))
      (node (ref "R226") (pin "2") (pinfunction "2_2") (pintype "passive"))
    )
    (net (code "40") (name "Net-(LED206-G)") (class "Default")
      (node (ref "LED206") (pin "4") (pinfunction "G_4") (pintype "passive"))
      (node (ref "R227") (pin "2") (pinfunction "2_2") (pintype "passive"))
    )
    (net (code "41") (name "Net-(LED206-R)") (class "Default")
      (node (ref "LED206") (pin "1") (pinfunction "R_1") (pintype "passive"))
      (node (ref "R228") (pin "2") (pinfunction "2_2") (pintype "passive"))
    )
    (net (code "42") (name "Net-(LED207-B)") (class "Default")
      (node (ref "LED207") (pin "3") (pinfunction "B_3") (pintype "passive"))
      (node (ref "R229") (pin "2") (pinfunction "2_2") (pintype "passive"))
    )
    (net (code "43") (name "Net-(LED207-G)") (class "Default")
      (node (ref "LED207") (pin "4") (pinfunction "G_4") (pintype "passive"))
      (node (ref "R230") (pin "2") (pinfunction "2_2") (pintype "passive"))
    )
    (net (code "44") (name "Net-(LED207-R)") (class "Default")
      (node (ref "LED207") (pin "1") (pinfunction "R_1") (pintype "passive"))
      (node (ref "R231") (pin "2") (pinfunction "2_2") (pintype "passive"))
    )
    (net (code "45") (name "Net-(LED208-B)") (class "Default")
      (node (ref "LED208") (pin "3") (pinfunction "B_3") (pintype "passive"))
      (node (ref "R232") (pin "2") (pinfunction "2_2") (pintype "passive"))
    )
    (net (code "46") (name "Net-(LED208-G)") (class "Default")
      (node (ref "LED208") (pin "4") (pinfunction "G_4") (pintype "passive"))
      (node (ref "R233") (pin "2") (pinfunction "2_2") (pintype "passive"))
    )
    (net (code "47") (name "Net-(LED208-R)") (class "Default")
      (node (ref "LED208") (pin "1") (pinfunction "R_1") (pintype "passive"))
      (node (ref "R234") (pin "2") (pinfunction "2_2") (pintype "passive"))
    )
    (net (code "48") (name "Net-(LED209-B)") (class "Default")
      (node (ref "LED209") (pin "3") (pinfunction "B_3") (pintype "passive"))
      (node (ref "R235") (pin "2") (pinfunction "2_2") (pintype "passive"))
    )
    (net (code "49") (name "Net-(LED209-G)") (class "Default")
      (node (ref "LED209") (pin "4") (pinfunction "G_4") (pintype "passive"))
      (node (ref "R236") (pin "2") (pinfunction "2_2") (pintype "passive"))
    )
    (net (code "50") (name "Net-(LED209-R)") (class "Default")
      (node (ref "LED209") (pin "1") (pinfunction "R_1") (pintype "passive"))
      (node (ref "R237") (pin "2") (pinfunction "2_2") (pintype "passive"))
    )
    (net (code "51") (name "Net-(LED210-B)") (class "Default")
      (node (ref "LED210") (pin "3") (pinfunction "B_3") (pintype "passive"))
      (node (ref "R238") (pin "2") (pinfunction "2_2") (pintype "passive"))
    )
    (net (code "52") (name "Net-(LED210-G)") (class "Default")
      (node (ref "LED210") (pin "4") (pinfunction "G_4") (pintype "passive"))
      (node (ref "R239") (pin "2") (pinfunction "2_2") (pintype "passive"))
    )
    (net (code "53") (name "Net-(LED210-R)") (class "Default")
      (node (ref "LED210") (pin "1") (pinfunction "R_1") (pintype "passive"))
      (node (ref "R240") (pin "2") (pinfunction "2_2") (pintype "passive"))
    )
    (net (code "54") (name "Net-(LED211-B)") (class "Default")
      (node (ref "LED211") (pin "3") (pinfunction "B_3") (pintype "passive"))
      (node (ref "R241") (pin "2") (pinfunction "2_2") (pintype "passive"))
    )
    (net (code "55") (name "Net-(LED211-G)") (class "Default")
      (node (ref "LED211") (pin "4") (pinfunction "G_4") (pintype "passive"))
      (node (ref "R242") (pin "2") (pinfunction "2_2") (pintype "passive"))
    )
    (net (code "56") (name "Net-(LED211-R)") (class "Default")
      (node (ref "LED211") (pin "1") (pinfunction "R_1") (pintype "passive"))
      (node (ref "R243") (pin "2") (pinfunction "2_2") (pintype "passive"))
    )
    (net (code "57") (name "Net-(U202-1A)") (class "Default")
      (node (ref "U202") (pin "4") (pinfunction "1A_4") (pintype "passive"))
      (node (ref "U203") (pin "2") (pinfunction "1B_2") (pintype "passive"))
    )
    (net (code "58") (name "Net-(U202-2A)") (class "Default")
      (node (ref "U202") (pin "7") (pinfunction "2A_7") (pintype "passive"))
      (node (ref "U203") (pin "5") (pinfunction "2B_5") (pintype "passive"))
    )
    (net (code "59") (name "Net-(U202-3A)") (class "Default")
      (node (ref "U202") (pin "9") (pinfunction "3A_9") (pintype "passive"))
      (node (ref "U203") (pin "11") (pinfunction "3B_11") (pintype "passive"))
    )
    (net (code "60") (name "Net-(U202-4A)") (class "Default")
      (node (ref "U202") (pin "12") (pinfunction "4A_12") (pintype "passive"))
      (node (ref "U203") (pin "14") (pinfunction "4B_14") (pintype "passive"))
    )
    (net (code "61") (name "VCC201A") (class "Default")
      (node (ref "C212") (pin "1") (pinfunction "1_1") (pintype "passive"))
      (node (ref "C215") (pin "2") (pinfunction "2_2") (pintype "passive"))
      (node (ref "I209") (pin "1") (pinfunction "1_1") (pintype "passive"))
      (node (ref "S201") (pin "14") (pinfunction "14_14") (pintype "passive"))
      (node (ref "S203") (pin "1") (pinfunction "COMMON_1") (pintype "passive"))
      (node (ref "U202") (pin "16") (pinfunction "Vcc_16") (pintype "passive"))
      (node (ref "U203") (pin "16") (pinfunction "Vcc_16") (pintype "passive"))
    )
    (net (code "62") (name "unconnected-(Reg201-NR{slash}Adj-Pad4)") (class "Default")
      (node (ref "Reg201") (pin "4") (pinfunction "NR/Adj_4") (pintype "passive+no_connect"))
    )
    (net (code "63") (name "unconnected-(S204-Pad1)") (class "Default")
      (node (ref "S204") (pin "1") (pinfunction "1_1") (pintype "passive"))
    )
    (net (code "64") (name "unconnected-(S204-Pad2)") (class "Default")
      (node (ref "S204") (pin "2") (pinfunction "2_2") (pintype "passive"))
    )
    (net (code "65") (name "unconnected-(S204-Pad3)") (class "Default")
      (node (ref "S204") (pin "3") (pinfunction "3_3") (pintype "passive"))
    )
    (net (code "66") (name "unconnected-(S204-Pad5)") (class "Default")
      (node (ref "S204") (pin "5") (pinfunction "5_5") (pintype "passive"))
    )
    (net (code "67") (name "unconnected-(S204-Pad6)") (class "Default")
      (node (ref "S204") (pin "6") (pinfunction "6_6") (pintype "passive"))
    )
    (net (code "68") (name "unconnected-(S204-Pad7)") (class "Default")
      (node (ref "S204") (pin "7") (pinfunction "7_7") (pintype "passive"))
    )
    (net (code "69") (name "unconnected-(S204-Pad8)") (class "Default")
      (node (ref "S204") (pin "8") (pinfunction "8_8") (pintype "passive"))
    )
    (net (code "70") (name "unconnected-(S204-Pad9)") (class "Default")
      (node (ref "S204") (pin "9") (pinfunction "9_9") (pintype "passive"))
    )
    (net (code "71") (name "unconnected-(S204-Pad10)") (class "Default")
      (node (ref "S204") (pin "10") (pinfunction "10_10") (pintype "passive"))
    )
    (net (code "72") (name "unconnected-(S204-Pad11)") (class "Default")
      (node (ref "S204") (pin "11") (pinfunction "11_11") (pintype "passive"))
    )
    (net (code "73") (name "unconnected-(S204-Pad12)") (class "Default")
      (node (ref "S204") (pin "12") (pinfunction "12_12") (pintype "passive"))
    )
    (net (code "74") (name "unconnected-(S204-Pad13)") (class "Default")
      (node (ref "S204") (pin "13") (pinfunction "13_13") (pintype "passive"))
    )
    (net (code "75") (name "unconnected-(S204-Pad14)") (class "Default")
      (node (ref "S204") (pin "14") (pinfunction "14_14") (pintype "passive"))
    )
  )
)
